# distortion-noise-and-ring-modulator-v1_0.net
KiCad netlist of a schematic drawn in EAGLE
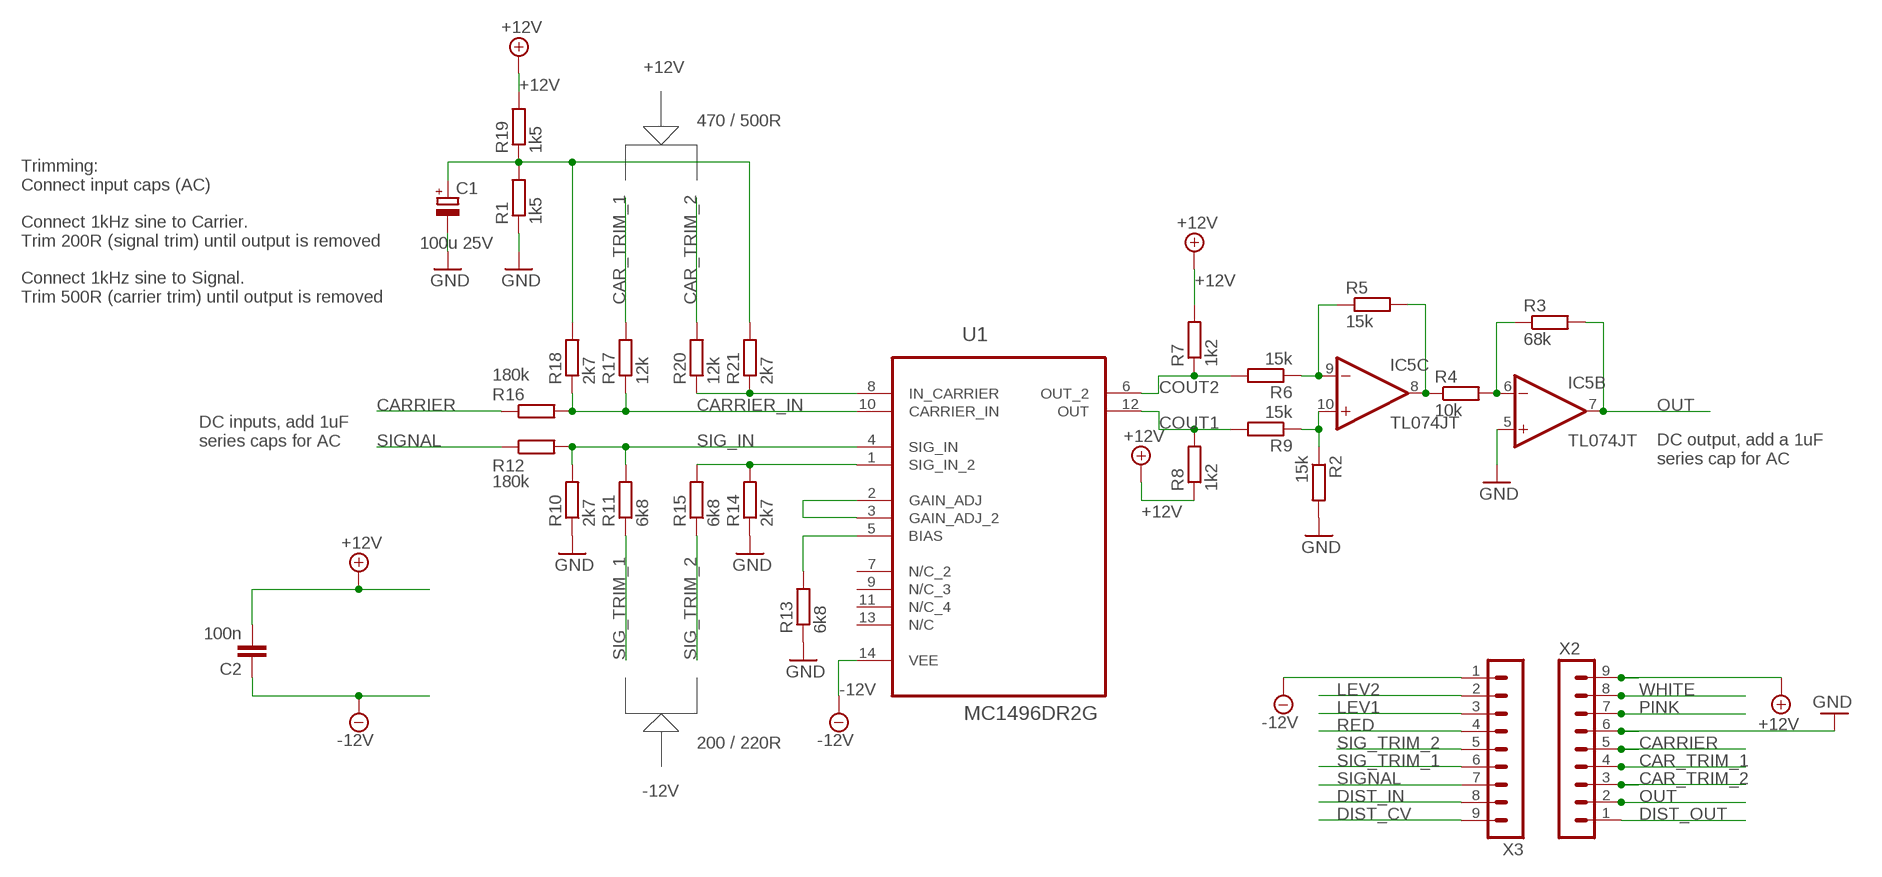
[diagram p0: schematic, sheet 1]
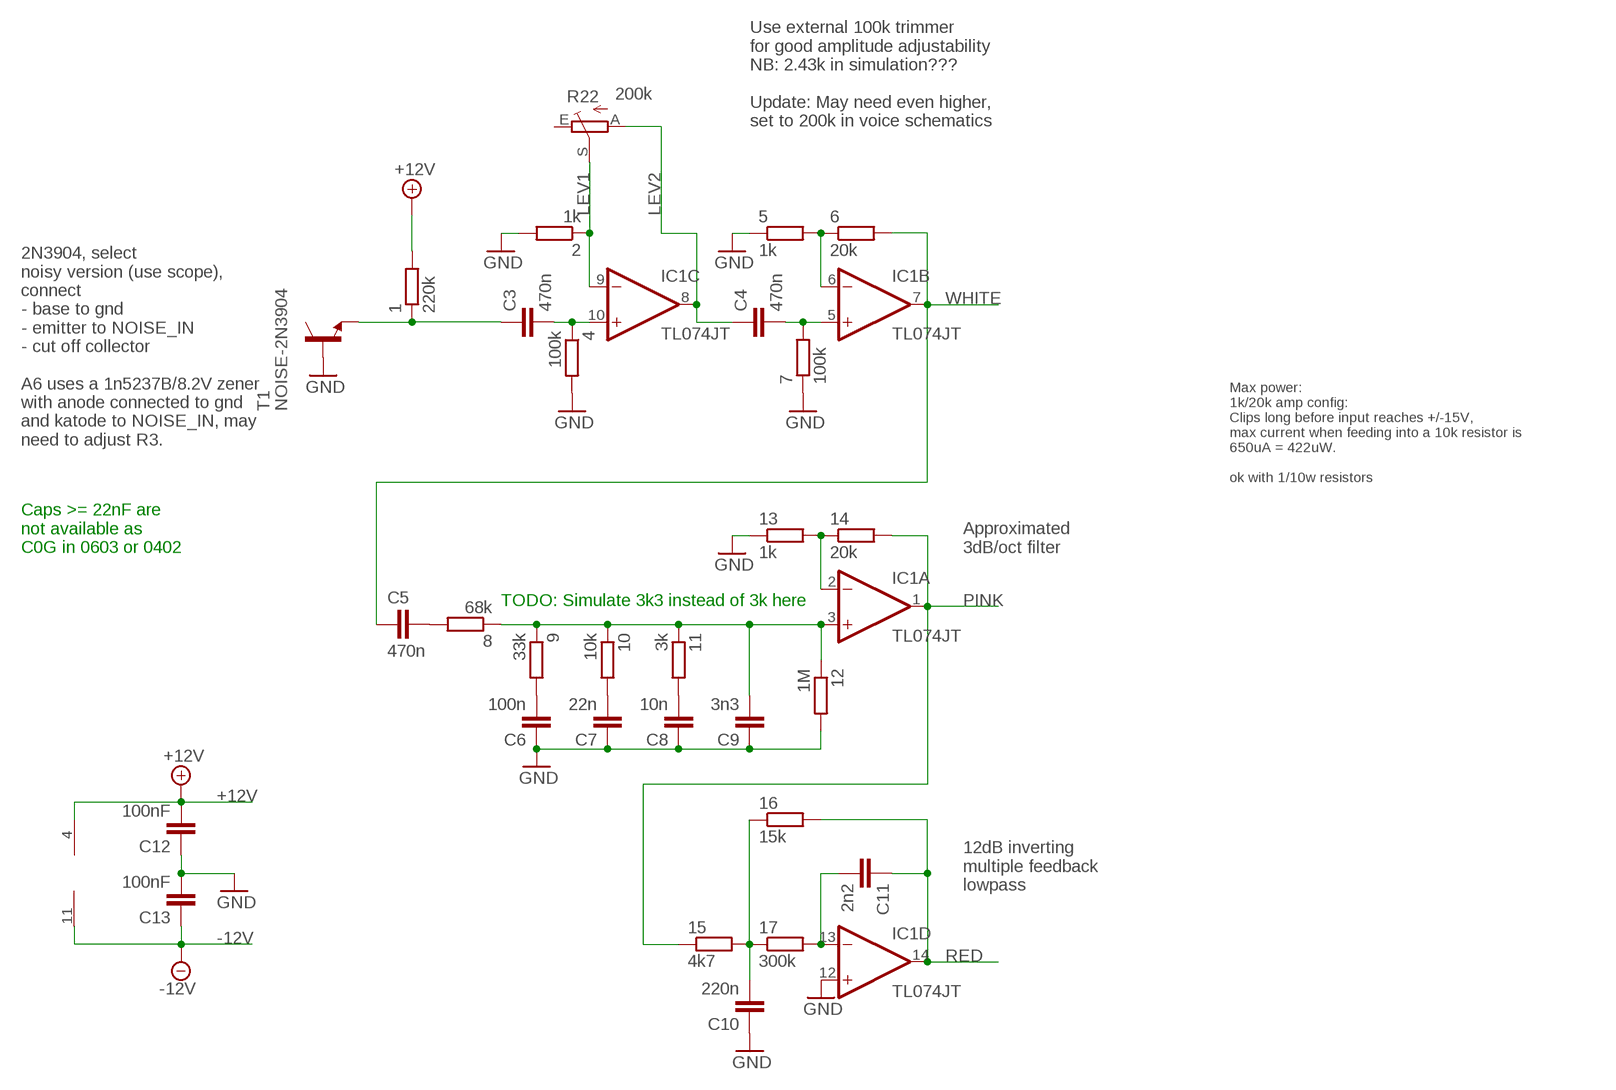
[diagram p1: schematic, sheet 2]
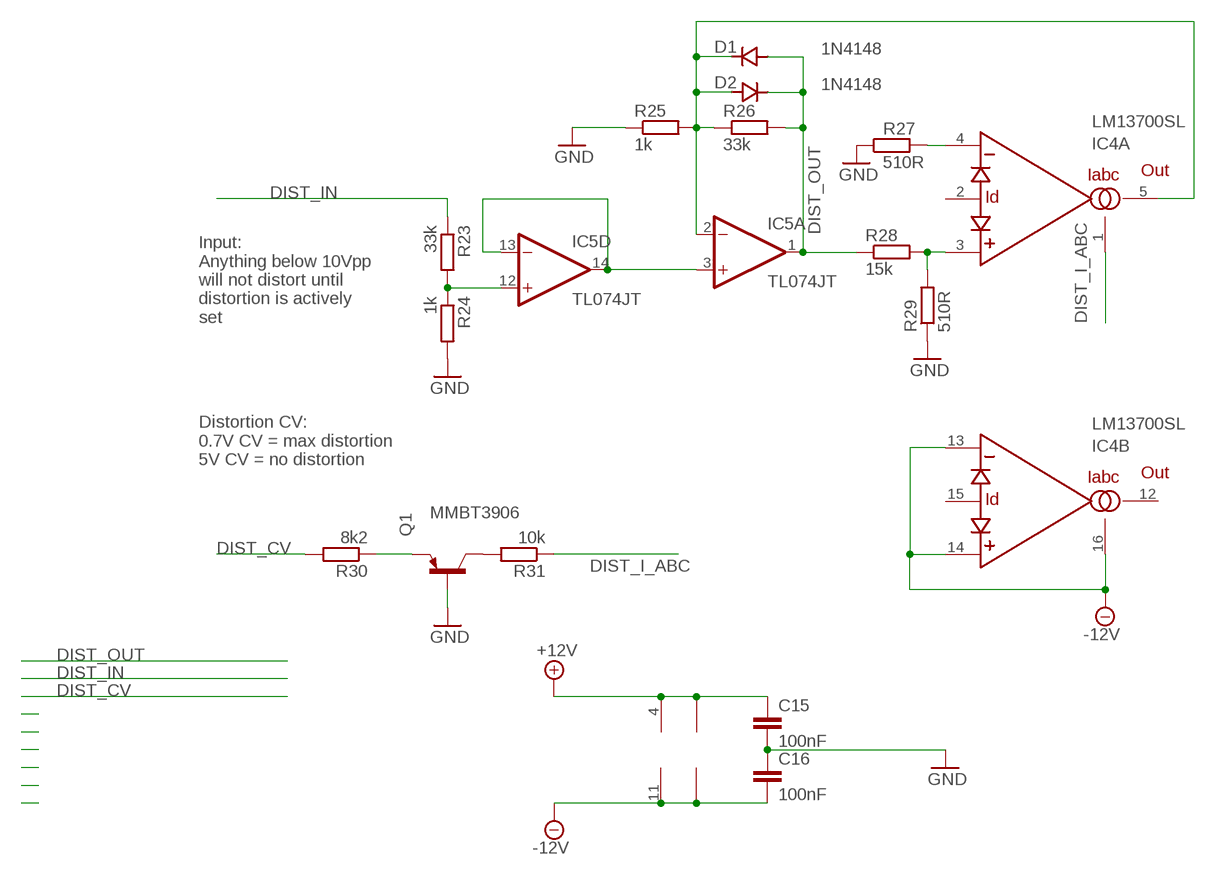
[diagram p2: schematic, sheet 3]

(export (version "E")
  (design (tool "Eeschema 10.0.6"))
  (components
    (comp (ref "1")
      (value "220k")
      (footprint "eagle-import:R0402")
      (libsource (lib "eagle-import") (part "R-EU_R0402"))
    )
    (comp (ref "2")
      (value "1k")
      (footprint "eagle-import:R0402")
      (libsource (lib "eagle-import") (part "R-EU_R0402"))
    )
    (comp (ref "4")
      (value "100k")
      (footprint "eagle-import:R0402")
      (libsource (lib "eagle-import") (part "R-EU_R0402"))
    )
    (comp (ref "5")
      (value "1k")
      (footprint "eagle-import:R0402")
      (libsource (lib "eagle-import") (part "R-EU_R0402"))
    )
    (comp (ref "6")
      (value "20k")
      (footprint "eagle-import:R0402")
      (libsource (lib "eagle-import") (part "R-EU_R0402"))
    )
    (comp (ref "7")
      (value "100k")
      (footprint "eagle-import:R0402")
      (libsource (lib "eagle-import") (part "R-EU_R0402"))
    )
    (comp (ref "8")
      (value "68k")
      (footprint "eagle-import:R0402")
      (libsource (lib "eagle-import") (part "R-EU_R0402"))
    )
    (comp (ref "9")
      (value "33k")
      (footprint "eagle-import:R0402")
      (libsource (lib "eagle-import") (part "R-EU_R0402"))
    )
    (comp (ref "10")
      (value "10k")
      (footprint "eagle-import:R0402")
      (libsource (lib "eagle-import") (part "R-EU_R0402"))
    )
    (comp (ref "11")
      (value "3k")
      (footprint "eagle-import:R0402")
      (libsource (lib "eagle-import") (part "R-EU_R0402"))
    )
    (comp (ref "12")
      (value "1M")
      (footprint "eagle-import:R0402")
      (libsource (lib "eagle-import") (part "R-EU_R0402"))
    )
    (comp (ref "13")
      (value "1k")
      (footprint "eagle-import:R0402")
      (libsource (lib "eagle-import") (part "R-EU_R0402"))
    )
    (comp (ref "14")
      (value "20k")
      (footprint "eagle-import:R0402")
      (libsource (lib "eagle-import") (part "R-EU_R0402"))
    )
    (comp (ref "15")
      (value "4k7")
      (footprint "eagle-import:R0402")
      (libsource (lib "eagle-import") (part "R-EU_R0402"))
    )
    (comp (ref "16")
      (value "15k")
      (footprint "eagle-import:R0402")
      (libsource (lib "eagle-import") (part "R-EU_R0402"))
    )
    (comp (ref "17")
      (value "300k")
      (footprint "eagle-import:R0402")
      (libsource (lib "eagle-import") (part "R-EU_R0402"))
    )
    (comp (ref "C3")
      (value "470n")
      (footprint "eagle-import:C0402-J")
      (libsource (lib "eagle-import") (part "C-EU-J"))
    )
    (comp (ref "C4")
      (value "470n")
      (footprint "eagle-import:C0402-J")
      (libsource (lib "eagle-import") (part "C-EU-J"))
    )
    (comp (ref "C5")
      (value "470n")
      (footprint "eagle-import:C0402-J")
      (libsource (lib "eagle-import") (part "C-EU-J"))
    )
    (comp (ref "C6")
      (value "100n")
      (footprint "eagle-import:C0402-J")
      (libsource (lib "eagle-import") (part "C-EU-J"))
    )
    (comp (ref "C7")
      (value "22n")
      (footprint "eagle-import:C0402-J")
      (libsource (lib "eagle-import") (part "C-EU-J"))
    )
    (comp (ref "C8")
      (value "10n")
      (footprint "eagle-import:C0402-J")
      (libsource (lib "eagle-import") (part "C-EU-J"))
    )
    (comp (ref "C9")
      (value "3n3")
      (footprint "eagle-import:C0402-J")
      (libsource (lib "eagle-import") (part "C-EU-J"))
    )
    (comp (ref "C10")
      (value "220n")
      (footprint "eagle-import:C0402-J")
      (libsource (lib "eagle-import") (part "C-EU-J"))
    )
    (comp (ref "C11")
      (value "2n2")
      (footprint "eagle-import:C0402-J")
      (libsource (lib "eagle-import") (part "C-EU-J"))
    )
    (comp (ref "C12")
      (value "100nF")
      (footprint "eagle-import:C0402-J")
      (libsource (lib "eagle-import") (part "C-EU-J"))
    )
    (comp (ref "C13")
      (value "100nF")
      (footprint "eagle-import:C0402-J")
      (libsource (lib "eagle-import") (part "C-EU-J"))
    )
    (comp (ref "IC1")
      (value "TL074JT")
      (footprint "eagle-import:TSSOP14J")
      (libsource (lib "eagle-import") (part "TL074JT"))
    )
    (comp (ref "R22")
      (value "200k")
      (footprint "eagle-import:S64W")
      (libsource (lib "eagle-import") (part "TRIM_EU-S64W"))
    )
    (comp (ref "T1")
      (value "NOISE-2N3904")
      (footprint "eagle-import:NOISE-2N3904-J")
      (libsource (lib "eagle-import") (part "NOISE-2N3904"))
    )
    (comp (ref "C15")
      (value "100nF")
      (footprint "eagle-import:C0402-J")
      (libsource (lib "eagle-import") (part "C-EU-J"))
    )
    (comp (ref "C16")
      (value "100nF")
      (footprint "eagle-import:C0402-J")
      (libsource (lib "eagle-import") (part "C-EU-J"))
    )
    (comp (ref "D1")
      (value "1N4148")
      (footprint "eagle-import:SOD323J")
      (libsource (lib "eagle-import") (part "1N4148SOD323"))
    )
    (comp (ref "D2")
      (value "1N4148")
      (footprint "eagle-import:SOD323J")
      (libsource (lib "eagle-import") (part "1N4148SOD323"))
    )
    (comp (ref "IC4")
      (value "LM13700SL")
      (footprint "eagle-import:SO16-NARROW-J")
      (libsource (lib "eagle-import") (part "LM13700SL"))
    )
    (comp (ref "IC5")
      (value "TL074JT")
      (footprint "eagle-import:TSSOP14J")
      (libsource (lib "eagle-import") (part "TL074JT"))
    )
    (comp (ref "Q1")
      (value "MMBT3906")
      (footprint "eagle-import:SOT23-BEC")
      (libsource (lib "eagle-import") (part "MMBT3906SMDLT1"))
    )
    (comp (ref "R23")
      (value "33k")
      (footprint "eagle-import:R0402")
      (libsource (lib "eagle-import") (part "R-EU_R0402"))
    )
    (comp (ref "R24")
      (value "1k")
      (footprint "eagle-import:R0402")
      (libsource (lib "eagle-import") (part "R-EU_R0402"))
    )
    (comp (ref "R25")
      (value "1k")
      (footprint "eagle-import:R0402")
      (libsource (lib "eagle-import") (part "R-EU_R0402"))
    )
    (comp (ref "R26")
      (value "33k")
      (footprint "eagle-import:R0402")
      (libsource (lib "eagle-import") (part "R-EU_R0402"))
    )
    (comp (ref "R27")
      (value "510R")
      (footprint "eagle-import:R0402")
      (libsource (lib "eagle-import") (part "R-EU_R0402"))
    )
    (comp (ref "R28")
      (value "15k")
      (footprint "eagle-import:R0402")
      (libsource (lib "eagle-import") (part "R-EU_R0402"))
    )
    (comp (ref "R29")
      (value "510R")
      (footprint "eagle-import:R0402")
      (libsource (lib "eagle-import") (part "R-EU_R0402"))
    )
    (comp (ref "R30")
      (value "8k2")
      (footprint "eagle-import:R0402")
      (libsource (lib "eagle-import") (part "R-EU_R0402"))
    )
    (comp (ref "R31")
      (value "10k")
      (footprint "eagle-import:R0402")
      (libsource (lib "eagle-import") (part "R-EU_R0402"))
    )
    (comp (ref "C1")
      (value "100u 25V")
      (footprint "eagle-import:E2-5")
      (libsource (lib "eagle-import") (part "CPOL-EUE2-5"))
    )
    (comp (ref "C2")
      (value "100n")
      (footprint "eagle-import:C0402-J")
      (libsource (lib "eagle-import") (part "C-EU-J"))
    )
    (comp (ref "R1")
      (value "1k5")
      (footprint "eagle-import:R0402")
      (libsource (lib "eagle-import") (part "R-EU_R0402"))
    )
    (comp (ref "R2")
      (value "15k")
      (footprint "eagle-import:R0402")
      (libsource (lib "eagle-import") (part "R-EU_R0402"))
    )
    (comp (ref "R3")
      (value "68k")
      (footprint "eagle-import:R0402")
      (libsource (lib "eagle-import") (part "R-EU_R0402"))
    )
    (comp (ref "R4")
      (value "10k")
      (footprint "eagle-import:R0402")
      (libsource (lib "eagle-import") (part "R-EU_R0402"))
    )
    (comp (ref "R5")
      (value "15k")
      (footprint "eagle-import:R0402")
      (libsource (lib "eagle-import") (part "R-EU_R0402"))
    )
    (comp (ref "R6")
      (value "15k")
      (footprint "eagle-import:R0402")
      (libsource (lib "eagle-import") (part "R-EU_R0402"))
    )
    (comp (ref "R7")
      (value "1k2")
      (footprint "eagle-import:R0402")
      (libsource (lib "eagle-import") (part "R-EU_R0402"))
    )
    (comp (ref "R8")
      (value "1k2")
      (footprint "eagle-import:R0402")
      (libsource (lib "eagle-import") (part "R-EU_R0402"))
    )
    (comp (ref "R9")
      (value "15k")
      (footprint "eagle-import:R0402")
      (libsource (lib "eagle-import") (part "R-EU_R0402"))
    )
    (comp (ref "R10")
      (value "2k7")
      (footprint "eagle-import:R0402")
      (libsource (lib "eagle-import") (part "R-EU_R0402"))
    )
    (comp (ref "R11")
      (value "6k8")
      (footprint "eagle-import:R0402")
      (libsource (lib "eagle-import") (part "R-EU_R0402"))
    )
    (comp (ref "R12")
      (value "180k")
      (footprint "eagle-import:R0402")
      (libsource (lib "eagle-import") (part "R-EU_R0402"))
    )
    (comp (ref "R13")
      (value "6k8")
      (footprint "eagle-import:R0402")
      (libsource (lib "eagle-import") (part "R-EU_R0402"))
    )
    (comp (ref "R14")
      (value "2k7")
      (footprint "eagle-import:R0402")
      (libsource (lib "eagle-import") (part "R-EU_R0402"))
    )
    (comp (ref "R15")
      (value "6k8")
      (footprint "eagle-import:R0402")
      (libsource (lib "eagle-import") (part "R-EU_R0402"))
    )
    (comp (ref "R16")
      (value "180k")
      (footprint "eagle-import:R0402")
      (libsource (lib "eagle-import") (part "R-EU_R0402"))
    )
    (comp (ref "R17")
      (value "12k")
      (footprint "eagle-import:R0402")
      (libsource (lib "eagle-import") (part "R-EU_R0402"))
    )
    (comp (ref "R18")
      (value "2k7")
      (footprint "eagle-import:R0402")
      (libsource (lib "eagle-import") (part "R-EU_R0402"))
    )
    (comp (ref "R19")
      (value "1k5")
      (footprint "eagle-import:R0402")
      (libsource (lib "eagle-import") (part "R-EU_R0402"))
    )
    (comp (ref "R20")
      (value "12k")
      (footprint "eagle-import:R0402")
      (libsource (lib "eagle-import") (part "R-EU_R0402"))
    )
    (comp (ref "R21")
      (value "2k7")
      (footprint "eagle-import:R0402")
      (libsource (lib "eagle-import") (part "R-EU_R0402"))
    )
    (comp (ref "U1")
      (value "MC1496DR2G")
      (footprint "eagle-import:SOIC127P600X175-14N")
      (libsource (lib "eagle-import") (part "MC1496DR2G"))
    )
    (comp (ref "X2")
      (value "MA09-1JN")
      (footprint "eagle-import:MA09N-1J")
      (libsource (lib "eagle-import") (part "MA09-1JN"))
    )
    (comp (ref "X3")
      (value "MA09-1JN")
      (footprint "eagle-import:MA09N-1J")
      (libsource (lib "eagle-import") (part "MA09-1JN"))
    )
  )
  (nets
    (net (code "1") (name "+12V") (class "Default")
      (node (ref "1") (pin "2") (pinfunction "2_2") (pintype "passive"))
      (node (ref "C12") (pin "2") (pinfunction "2_2") (pintype "passive"))
      (node (ref "C15") (pin "1") (pinfunction "1_1") (pintype "passive"))
      (node (ref "C2") (pin "2") (pinfunction "2_2") (pintype "passive"))
      (node (ref "IC1") (pin "4") (pinfunction "V+_4") (pintype "power_in"))
      (node (ref "IC4") (pin "11") (pinfunction "V+_11") (pintype "bidirectional"))
      (node (ref "IC5") (pin "4") (pinfunction "V+_4") (pintype "power_in"))
      (node (ref "R19") (pin "2") (pinfunction "2_2") (pintype "passive"))
      (node (ref "R7") (pin "2") (pinfunction "2_2") (pintype "passive"))
      (node (ref "R8") (pin "1") (pinfunction "1_1") (pintype "passive"))
      (node (ref "X2") (pin "9") (pinfunction "9_9") (pintype "passive"))
    )
    (net (code "2") (name "-12V") (class "Default")
      (node (ref "C13") (pin "1") (pinfunction "1_1") (pintype "passive"))
      (node (ref "C16") (pin "2") (pinfunction "2_2") (pintype "passive"))
      (node (ref "C2") (pin "1") (pinfunction "1_1") (pintype "passive"))
      (node (ref "IC1") (pin "11") (pinfunction "V-_11") (pintype "power_in"))
      (node (ref "IC4") (pin "13") (pinfunction "-IN_13") (pintype "bidirectional"))
      (node (ref "IC4") (pin "14") (pinfunction "+IN_14") (pintype "bidirectional"))
      (node (ref "IC4") (pin "16") (pinfunction "IABC_16") (pintype "bidirectional"))
      (node (ref "IC4") (pin "6") (pinfunction "V-_6") (pintype "bidirectional"))
      (node (ref "IC5") (pin "11") (pinfunction "V-_11") (pintype "power_in"))
      (node (ref "U1") (pin "14") (pinfunction "VEE_14") (pintype "passive"))
      (node (ref "X3") (pin "1") (pinfunction "1_1") (pintype "passive"))
    )
    (net (code "3") (name "CARRIER") (class "Default")
      (node (ref "R16") (pin "1") (pinfunction "1_1") (pintype "passive"))
      (node (ref "X2") (pin "5") (pinfunction "5_5") (pintype "passive"))
    )
    (net (code "4") (name "CARRIER_IN") (class "Default")
      (node (ref "R16") (pin "2") (pinfunction "2_2") (pintype "passive"))
      (node (ref "R17") (pin "1") (pinfunction "1_1") (pintype "passive"))
      (node (ref "R18") (pin "1") (pinfunction "1_1") (pintype "passive"))
      (node (ref "U1") (pin "10") (pinfunction "CARRIER_IN_10") (pintype "power_in"))
    )
    (net (code "5") (name "CAR_TRIM_1") (class "Default")
      (node (ref "R17") (pin "2") (pinfunction "2_2") (pintype "passive"))
      (node (ref "X2") (pin "4") (pinfunction "4_4") (pintype "passive"))
    )
    (net (code "6") (name "CAR_TRIM_2") (class "Default")
      (node (ref "R20") (pin "2") (pinfunction "2_2") (pintype "passive"))
      (node (ref "X2") (pin "3") (pinfunction "3_3") (pintype "passive"))
    )
    (net (code "7") (name "COUT1") (class "Default")
      (node (ref "R8") (pin "2") (pinfunction "2_2") (pintype "passive"))
      (node (ref "R9") (pin "2") (pinfunction "2_2") (pintype "passive"))
      (node (ref "U1") (pin "12") (pinfunction "OUT_12") (pintype "output"))
    )
    (net (code "8") (name "COUT2") (class "Default")
      (node (ref "R6") (pin "2") (pinfunction "2_2") (pintype "passive"))
      (node (ref "R7") (pin "1") (pinfunction "1_1") (pintype "passive"))
      (node (ref "U1") (pin "6") (pinfunction "OUT_2_6") (pintype "output"))
    )
    (net (code "9") (name "DIST_CV") (class "Default")
      (node (ref "R30") (pin "2") (pinfunction "2_2") (pintype "passive"))
      (node (ref "X3") (pin "9") (pinfunction "9_9") (pintype "passive"))
    )
    (net (code "10") (name "DIST_IN") (class "Default")
      (node (ref "R23") (pin "1") (pinfunction "1_1") (pintype "passive"))
      (node (ref "X3") (pin "8") (pinfunction "8_8") (pintype "passive"))
    )
    (net (code "11") (name "DIST_I_ABC") (class "Default")
      (node (ref "IC4") (pin "1") (pinfunction "IABC_1") (pintype "bidirectional"))
      (node (ref "R31") (pin "1") (pinfunction "1_1") (pintype "passive"))
    )
    (net (code "12") (name "DIST_OUT") (class "Default")
      (node (ref "D1") (pin "2") (pinfunction "A_2") (pintype "passive"))
      (node (ref "D2") (pin "1") (pinfunction "C_1") (pintype "passive"))
      (node (ref "IC5") (pin "1") (pinfunction "OUT_1") (pintype "output"))
      (node (ref "R26") (pin "2") (pinfunction "2_2") (pintype "passive"))
      (node (ref "R28") (pin "1") (pinfunction "1_1") (pintype "passive"))
      (node (ref "X2") (pin "1") (pinfunction "1_1") (pintype "passive"))
    )
    (net (code "13") (name "GND") (class "Default")
      (node (ref "12") (pin "2") (pinfunction "2_2") (pintype "passive"))
      (node (ref "13") (pin "1") (pinfunction "1_1") (pintype "passive"))
      (node (ref "2") (pin "2") (pinfunction "2_2") (pintype "passive"))
      (node (ref "4") (pin "2") (pinfunction "2_2") (pintype "passive"))
      (node (ref "5") (pin "1") (pinfunction "1_1") (pintype "passive"))
      (node (ref "7") (pin "1") (pinfunction "1_1") (pintype "passive"))
      (node (ref "C1") (pin "-") (pinfunction "-_-") (pintype "passive"))
      (node (ref "C10") (pin "1") (pinfunction "1_1") (pintype "passive"))
      (node (ref "C12") (pin "1") (pinfunction "1_1") (pintype "passive"))
      (node (ref "C13") (pin "2") (pinfunction "2_2") (pintype "passive"))
      (node (ref "C15") (pin "2") (pinfunction "2_2") (pintype "passive"))
      (node (ref "C16") (pin "1") (pinfunction "1_1") (pintype "passive"))
      (node (ref "C6") (pin "1") (pinfunction "1_1") (pintype "passive"))
      (node (ref "C7") (pin "1") (pinfunction "1_1") (pintype "passive"))
      (node (ref "C8") (pin "1") (pinfunction "1_1") (pintype "passive"))
      (node (ref "C9") (pin "1") (pinfunction "1_1") (pintype "passive"))
      (node (ref "IC1") (pin "12") (pinfunction "+IN_12") (pintype "input"))
      (node (ref "IC5") (pin "5") (pinfunction "+IN_5") (pintype "input"))
      (node (ref "Q1") (pin "B") (pinfunction "B_B") (pintype "passive"))
      (node (ref "R1") (pin "1") (pinfunction "1_1") (pintype "passive"))
      (node (ref "R10") (pin "1") (pinfunction "1_1") (pintype "passive"))
      (node (ref "R13") (pin "1") (pinfunction "1_1") (pintype "passive"))
      (node (ref "R14") (pin "1") (pinfunction "1_1") (pintype "passive"))
      (node (ref "R2") (pin "2") (pinfunction "2_2") (pintype "passive"))
      (node (ref "R24") (pin "2") (pinfunction "2_2") (pintype "passive"))
      (node (ref "R25") (pin "1") (pinfunction "1_1") (pintype "passive"))
      (node (ref "R27") (pin "1") (pinfunction "1_1") (pintype "passive"))
      (node (ref "R29") (pin "1") (pinfunction "1_1") (pintype "passive"))
      (node (ref "T1") (pin "B") (pinfunction "B_B") (pintype "passive"))
      (node (ref "X2") (pin "6") (pinfunction "6_6") (pintype "passive"))
    )
    (net (code "14") (name "LEV1") (class "Default")
      (node (ref "2") (pin "1") (pinfunction "1_1") (pintype "passive"))
      (node (ref "IC1") (pin "9") (pinfunction "-IN_9") (pintype "input"))
      (node (ref "R22") (pin "S") (pinfunction "S_S") (pintype "passive"))
      (node (ref "X3") (pin "3") (pinfunction "3_3") (pintype "passive"))
    )
    (net (code "15") (name "LEV2") (class "Default")
      (node (ref "C4") (pin "1") (pinfunction "1_1") (pintype "passive"))
      (node (ref "IC1") (pin "8") (pinfunction "OUT_8") (pintype "output"))
      (node (ref "R22") (pin "A") (pinfunction "A_A") (pintype "passive"))
      (node (ref "X3") (pin "2") (pinfunction "2_2") (pintype "passive"))
    )
    (net (code "16") (name "Net-(1-Pad1)") (class "Default")
      (node (ref "1") (pin "1") (pinfunction "1_1") (pintype "passive"))
      (node (ref "C3") (pin "1") (pinfunction "1_1") (pintype "passive"))
      (node (ref "T1") (pin "E") (pinfunction "E_E") (pintype "passive"))
    )
    (net (code "17") (name "Net-(8-Pad2)") (class "Default")
      (node (ref "8") (pin "2") (pinfunction "2_2") (pintype "passive"))
      (node (ref "C5") (pin "2") (pinfunction "2_2") (pintype "passive"))
    )
    (net (code "18") (name "Net-(9-Pad2)") (class "Default")
      (node (ref "9") (pin "2") (pinfunction "2_2") (pintype "passive"))
      (node (ref "C6") (pin "2") (pinfunction "2_2") (pintype "passive"))
    )
    (net (code "19") (name "Net-(10-Pad2)") (class "Default")
      (node (ref "10") (pin "2") (pinfunction "2_2") (pintype "passive"))
      (node (ref "C7") (pin "2") (pinfunction "2_2") (pintype "passive"))
    )
    (net (code "20") (name "Net-(11-Pad2)") (class "Default")
      (node (ref "11") (pin "2") (pinfunction "2_2") (pintype "passive"))
      (node (ref "C8") (pin "2") (pinfunction "2_2") (pintype "passive"))
    )
    (net (code "21") (name "Net-(15-Pad2)") (class "Default")
      (node (ref "15") (pin "2") (pinfunction "2_2") (pintype "passive"))
      (node (ref "16") (pin "1") (pinfunction "1_1") (pintype "passive"))
      (node (ref "17") (pin "1") (pinfunction "1_1") (pintype "passive"))
      (node (ref "C10") (pin "2") (pinfunction "2_2") (pintype "passive"))
    )
    (net (code "22") (name "Net-(C1-Pad+)") (class "Default")
      (node (ref "C1") (pin "+") (pinfunction "+_+") (pintype "passive"))
      (node (ref "R1") (pin "2") (pinfunction "2_2") (pintype "passive"))
      (node (ref "R18") (pin "2") (pinfunction "2_2") (pintype "passive"))
      (node (ref "R19") (pin "1") (pinfunction "1_1") (pintype "passive"))
      (node (ref "R21") (pin "2") (pinfunction "2_2") (pintype "passive"))
    )
    (net (code "23") (name "Net-(D1-C)") (class "Default")
      (node (ref "D1") (pin "1") (pinfunction "C_1") (pintype "passive"))
      (node (ref "D2") (pin "2") (pinfunction "A_2") (pintype "passive"))
      (node (ref "IC4") (pin "5") (pinfunction "OUT_5") (pintype "bidirectional"))
      (node (ref "IC5") (pin "2") (pinfunction "-IN_2") (pintype "input"))
      (node (ref "R25") (pin "2") (pinfunction "2_2") (pintype "passive"))
      (node (ref "R26") (pin "1") (pinfunction "1_1") (pintype "passive"))
    )
    (net (code "24") (name "Net-(IC1A-+IN)") (class "Default")
      (node (ref "10") (pin "1") (pinfunction "1_1") (pintype "passive"))
      (node (ref "11") (pin "1") (pinfunction "1_1") (pintype "passive"))
      (node (ref "12") (pin "1") (pinfunction "1_1") (pintype "passive"))
      (node (ref "8") (pin "1") (pinfunction "1_1") (pintype "passive"))
      (node (ref "9") (pin "1") (pinfunction "1_1") (pintype "passive"))
      (node (ref "C9") (pin "2") (pinfunction "2_2") (pintype "passive"))
      (node (ref "IC1") (pin "3") (pinfunction "+IN_3") (pintype "input"))
    )
    (net (code "25") (name "Net-(IC1A--IN)") (class "Default")
      (node (ref "13") (pin "2") (pinfunction "2_2") (pintype "passive"))
      (node (ref "14") (pin "1") (pinfunction "1_1") (pintype "passive"))
      (node (ref "IC1") (pin "2") (pinfunction "-IN_2") (pintype "input"))
    )
    (net (code "26") (name "Net-(IC1B-+IN)") (class "Default")
      (node (ref "7") (pin "2") (pinfunction "2_2") (pintype "passive"))
      (node (ref "C4") (pin "2") (pinfunction "2_2") (pintype "passive"))
      (node (ref "IC1") (pin "5") (pinfunction "+IN_5") (pintype "input"))
    )
    (net (code "27") (name "Net-(IC1B--IN)") (class "Default")
      (node (ref "5") (pin "2") (pinfunction "2_2") (pintype "passive"))
      (node (ref "6") (pin "1") (pinfunction "1_1") (pintype "passive"))
      (node (ref "IC1") (pin "6") (pinfunction "-IN_6") (pintype "input"))
    )
    (net (code "28") (name "Net-(IC1C-+IN)") (class "Default")
      (node (ref "4") (pin "1") (pinfunction "1_1") (pintype "passive"))
      (node (ref "C3") (pin "2") (pinfunction "2_2") (pintype "passive"))
      (node (ref "IC1") (pin "10") (pinfunction "+IN_10") (pintype "input"))
    )
    (net (code "29") (name "Net-(IC1D--IN)") (class "Default")
      (node (ref "17") (pin "2") (pinfunction "2_2") (pintype "passive"))
      (node (ref "C11") (pin "2") (pinfunction "2_2") (pintype "passive"))
      (node (ref "IC1") (pin "13") (pinfunction "-IN_13") (pintype "input"))
    )
    (net (code "30") (name "Net-(IC4A-+IN)") (class "Default")
      (node (ref "IC4") (pin "3") (pinfunction "+IN_3") (pintype "bidirectional"))
      (node (ref "R28") (pin "2") (pinfunction "2_2") (pintype "passive"))
      (node (ref "R29") (pin "2") (pinfunction "2_2") (pintype "passive"))
    )
    (net (code "31") (name "Net-(IC4A--IN)") (class "Default")
      (node (ref "IC4") (pin "4") (pinfunction "-IN_4") (pintype "bidirectional"))
      (node (ref "R27") (pin "2") (pinfunction "2_2") (pintype "passive"))
    )
    (net (code "32") (name "Net-(IC5A-+IN)") (class "Default")
      (node (ref "IC5") (pin "13") (pinfunction "-IN_13") (pintype "input"))
      (node (ref "IC5") (pin "14") (pinfunction "OUT_14") (pintype "output"))
      (node (ref "IC5") (pin "3") (pinfunction "+IN_3") (pintype "input"))
    )
    (net (code "33") (name "Net-(IC5B--IN)") (class "Default")
      (node (ref "IC5") (pin "6") (pinfunction "-IN_6") (pintype "input"))
      (node (ref "R3") (pin "1") (pinfunction "1_1") (pintype "passive"))
      (node (ref "R4") (pin "2") (pinfunction "2_2") (pintype "passive"))
    )
    (net (code "34") (name "Net-(IC5C-+IN)") (class "Default")
      (node (ref "IC5") (pin "10") (pinfunction "+IN_10") (pintype "input"))
      (node (ref "R2") (pin "1") (pinfunction "1_1") (pintype "passive"))
      (node (ref "R9") (pin "1") (pinfunction "1_1") (pintype "passive"))
    )
    (net (code "35") (name "Net-(IC5C--IN)") (class "Default")
      (node (ref "IC5") (pin "9") (pinfunction "-IN_9") (pintype "input"))
      (node (ref "R5") (pin "1") (pinfunction "1_1") (pintype "passive"))
      (node (ref "R6") (pin "1") (pinfunction "1_1") (pintype "passive"))
    )
    (net (code "36") (name "Net-(IC5C-OUT)") (class "Default")
      (node (ref "IC5") (pin "8") (pinfunction "OUT_8") (pintype "output"))
      (node (ref "R4") (pin "1") (pinfunction "1_1") (pintype "passive"))
      (node (ref "R5") (pin "2") (pinfunction "2_2") (pintype "passive"))
    )
    (net (code "37") (name "Net-(IC5D-+IN)") (class "Default")
      (node (ref "IC5") (pin "12") (pinfunction "+IN_12") (pintype "input"))
      (node (ref "R23") (pin "2") (pinfunction "2_2") (pintype "passive"))
      (node (ref "R24") (pin "1") (pinfunction "1_1") (pintype "passive"))
    )
    (net (code "38") (name "Net-(Q1-PadC)") (class "Default")
      (node (ref "Q1") (pin "C") (pinfunction "C_C") (pintype "passive"))
      (node (ref "R31") (pin "2") (pinfunction "2_2") (pintype "passive"))
    )
    (net (code "39") (name "Net-(Q1-PadE)") (class "Default")
      (node (ref "Q1") (pin "E") (pinfunction "E_E") (pintype "passive"))
      (node (ref "R30") (pin "1") (pinfunction "1_1") (pintype "passive"))
    )
    (net (code "40") (name "Net-(U1-BIAS)") (class "Default")
      (node (ref "R13") (pin "2") (pinfunction "2_2") (pintype "passive"))
      (node (ref "U1") (pin "5") (pinfunction "BIAS_5") (pintype "input"))
    )
    (net (code "41") (name "Net-(U1-GAIN_ADJ)") (class "Default")
      (node (ref "U1") (pin "2") (pinfunction "GAIN_ADJ_2") (pintype "input"))
      (node (ref "U1") (pin "3") (pinfunction "GAIN_ADJ_2_3") (pintype "input"))
    )
    (net (code "42") (name "Net-(U1-IN_CARRIER)") (class "Default")
      (node (ref "R20") (pin "1") (pinfunction "1_1") (pintype "passive"))
      (node (ref "R21") (pin "1") (pinfunction "1_1") (pintype "passive"))
      (node (ref "U1") (pin "8") (pinfunction "IN_CARRIER_8") (pintype "power_in"))
    )
    (net (code "43") (name "Net-(U1-SIG_IN_2)") (class "Default")
      (node (ref "R14") (pin "2") (pinfunction "2_2") (pintype "passive"))
      (node (ref "R15") (pin "2") (pinfunction "2_2") (pintype "passive"))
      (node (ref "U1") (pin "1") (pinfunction "SIG_IN_2_1") (pintype "input"))
    )
    (net (code "44") (name "OUT") (class "Default")
      (node (ref "IC5") (pin "7") (pinfunction "OUT_7") (pintype "output"))
      (node (ref "R3") (pin "2") (pinfunction "2_2") (pintype "passive"))
      (node (ref "X2") (pin "2") (pinfunction "2_2") (pintype "passive"))
    )
    (net (code "45") (name "PINK") (class "Default")
      (node (ref "14") (pin "2") (pinfunction "2_2") (pintype "passive"))
      (node (ref "15") (pin "1") (pinfunction "1_1") (pintype "passive"))
      (node (ref "IC1") (pin "1") (pinfunction "OUT_1") (pintype "output"))
      (node (ref "X2") (pin "7") (pinfunction "7_7") (pintype "passive"))
    )
    (net (code "46") (name "RED") (class "Default")
      (node (ref "16") (pin "2") (pinfunction "2_2") (pintype "passive"))
      (node (ref "C11") (pin "1") (pinfunction "1_1") (pintype "passive"))
      (node (ref "IC1") (pin "14") (pinfunction "OUT_14") (pintype "output"))
      (node (ref "X3") (pin "4") (pinfunction "4_4") (pintype "passive"))
    )
    (net (code "47") (name "SIGNAL") (class "Default")
      (node (ref "R12") (pin "1") (pinfunction "1_1") (pintype "passive"))
      (node (ref "X3") (pin "7") (pinfunction "7_7") (pintype "passive"))
    )
    (net (code "48") (name "SIG_IN") (class "Default")
      (node (ref "R10") (pin "2") (pinfunction "2_2") (pintype "passive"))
      (node (ref "R11") (pin "2") (pinfunction "2_2") (pintype "passive"))
      (node (ref "R12") (pin "2") (pinfunction "2_2") (pintype "passive"))
      (node (ref "U1") (pin "4") (pinfunction "SIG_IN_4") (pintype "input"))
    )
    (net (code "49") (name "SIG_TRIM_1") (class "Default")
      (node (ref "R11") (pin "1") (pinfunction "1_1") (pintype "passive"))
      (node (ref "X3") (pin "6") (pinfunction "6_6") (pintype "passive"))
    )
    (net (code "50") (name "SIG_TRIM_2") (class "Default")
      (node (ref "R15") (pin "1") (pinfunction "1_1") (pintype "passive"))
      (node (ref "X3") (pin "5") (pinfunction "5_5") (pintype "passive"))
    )
    (net (code "51") (name "WHITE") (class "Default")
      (node (ref "6") (pin "2") (pinfunction "2_2") (pintype "passive"))
      (node (ref "C5") (pin "1") (pinfunction "1_1") (pintype "passive"))
      (node (ref "IC1") (pin "7") (pinfunction "OUT_7") (pintype "output"))
      (node (ref "X2") (pin "8") (pinfunction "8_8") (pintype "passive"))
    )
    (net (code "52") (name "unconnected-(IC4A-ID-Pad2)") (class "Default")
      (node (ref "IC4") (pin "2") (pinfunction "ID_2") (pintype "bidirectional"))
    )
    (net (code "53") (name "unconnected-(IC4B-ID-Pad15)") (class "Default")
      (node (ref "IC4") (pin "15") (pinfunction "ID_15") (pintype "bidirectional"))
    )
    (net (code "54") (name "unconnected-(IC4B-OUT-Pad12)") (class "Default")
      (node (ref "IC4") (pin "12") (pinfunction "OUT_12") (pintype "bidirectional"))
    )
    (net (code "55") (name "unconnected-(R22-PadE)") (class "Default")
      (node (ref "R22") (pin "E") (pinfunction "E_E") (pintype "passive"))
    )
    (net (code "56") (name "unconnected-(U1-N{slash}C-Pad13)") (class "Default")
      (node (ref "U1") (pin "13") (pinfunction "N/C_13") (pintype "no_connect"))
    )
    (net (code "57") (name "unconnected-(U1-N{slash}C_2-Pad7)") (class "Default")
      (node (ref "U1") (pin "7") (pinfunction "N/C_2_7") (pintype "no_connect"))
    )
    (net (code "58") (name "unconnected-(U1-N{slash}C_3-Pad9)") (class "Default")
      (node (ref "U1") (pin "9") (pinfunction "N/C_3_9") (pintype "no_connect"))
    )
    (net (code "59") (name "unconnected-(U1-N{slash}C_4-Pad11)") (class "Default")
      (node (ref "U1") (pin "11") (pinfunction "N/C_4_11") (pintype "no_connect"))
    )
  )
)
